# wespi-nano_4.net
KiCad netlist of a schematic drawn in EAGLE
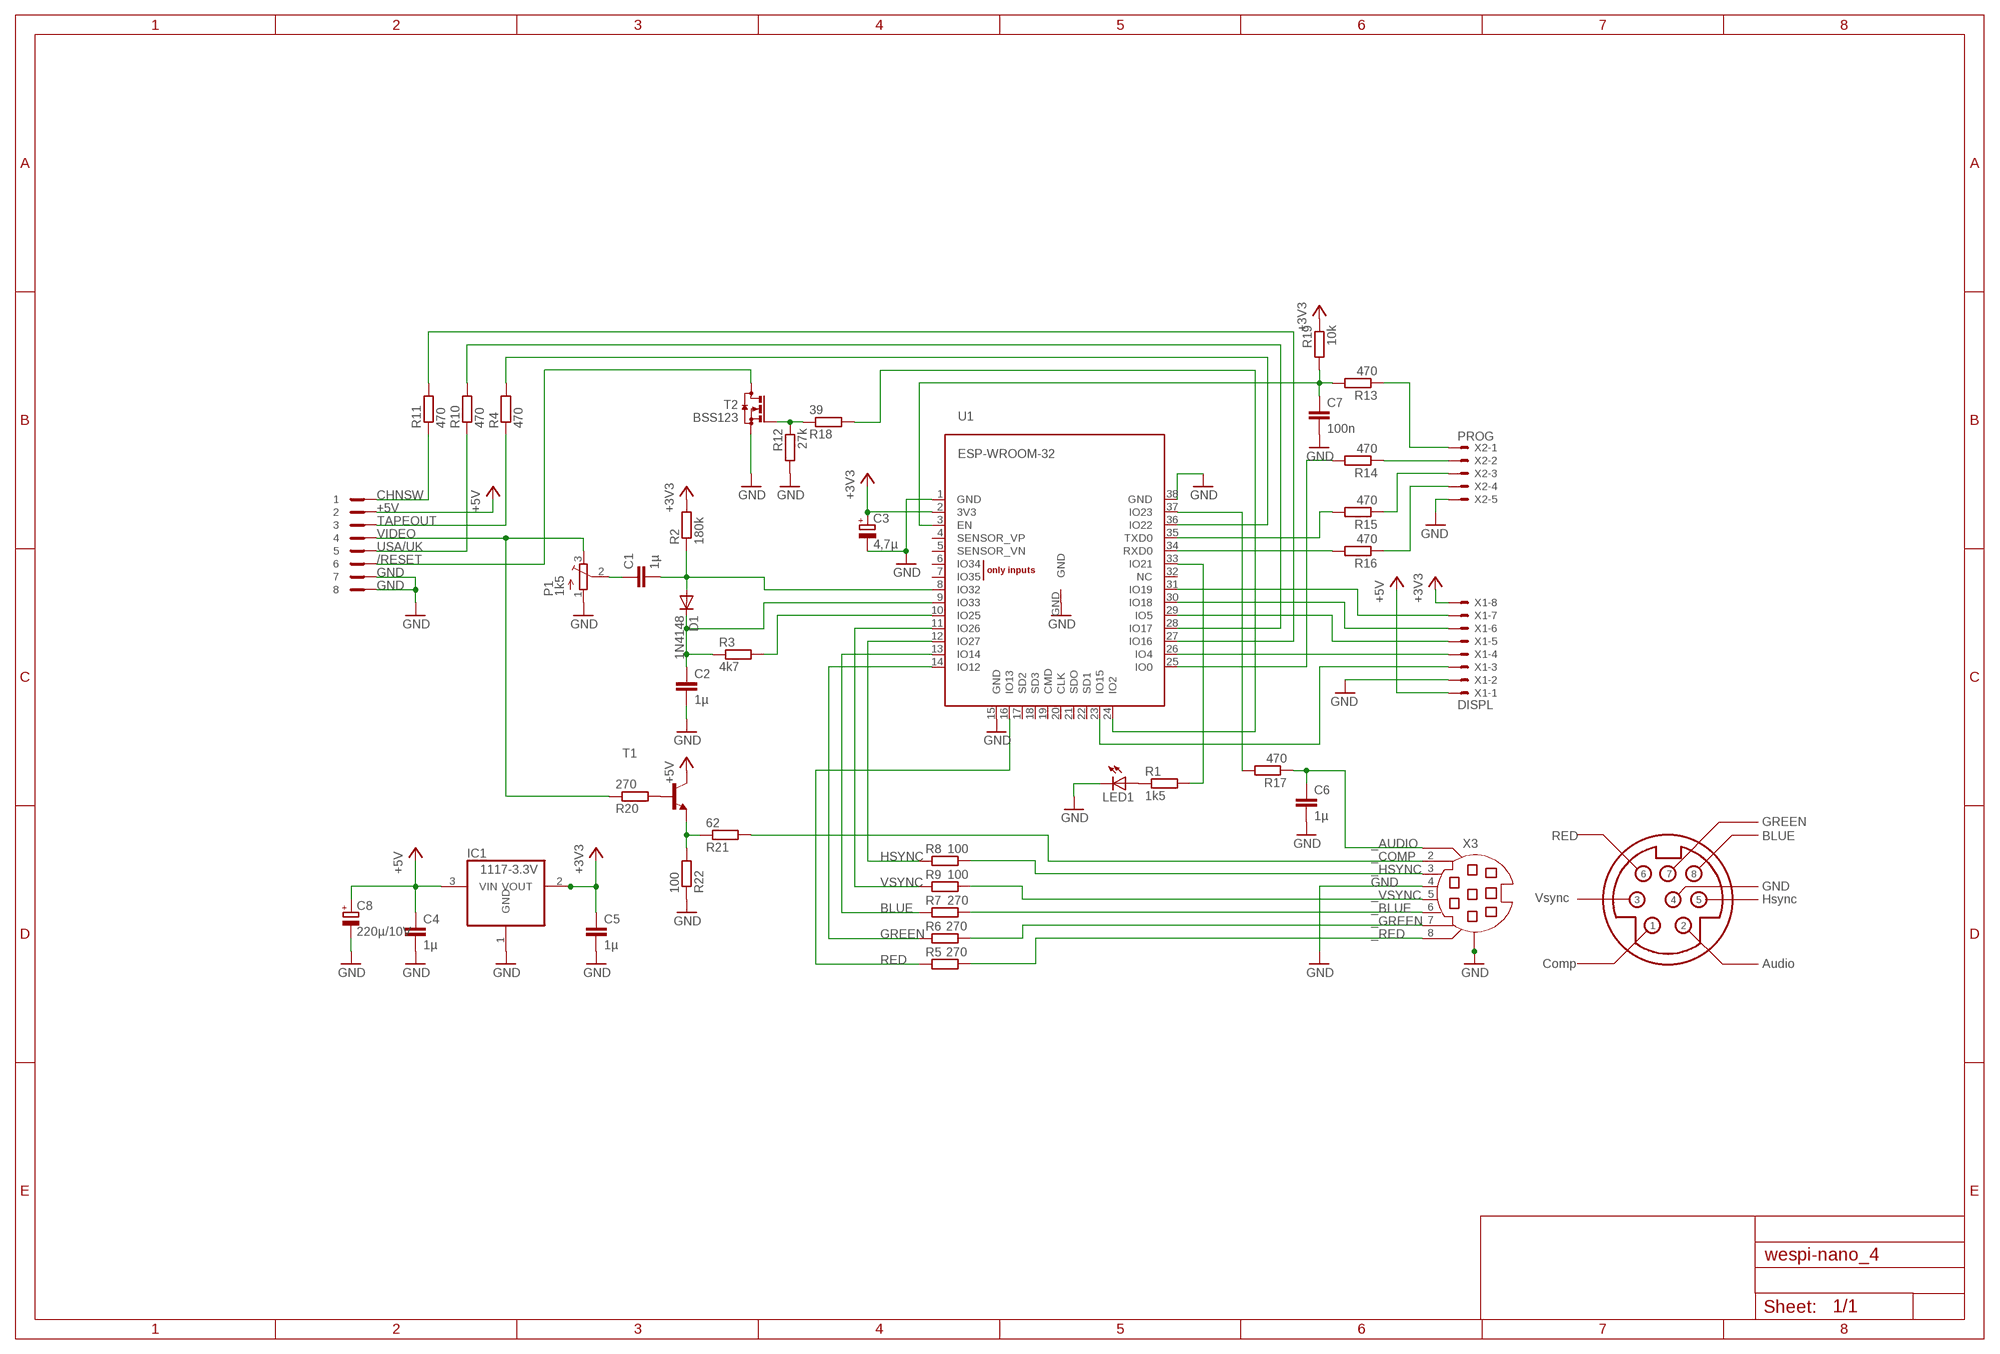
[diagram p0: schematic, sheet 1]

(export (version "E")
  (design (tool "Eeschema 10.0.6"))
  (components
    (comp (ref "C1")
      (value "1µ")
      (footprint "eagle-import:C0805")
      (libsource (lib "eagle-import") (part "C-EUC0805"))
    )
    (comp (ref "C2")
      (value "1µ")
      (footprint "eagle-import:C0805")
      (libsource (lib "eagle-import") (part "C-EUC0805"))
    )
    (comp (ref "C3")
      (value "4,7µ")
      (footprint "eagle-import:153CLV-0405")
      (libsource (lib "eagle-import") (part "CPOL-EU153CLV-0405"))
    )
    (comp (ref "C4")
      (value "1µ")
      (footprint "eagle-import:C0805")
      (libsource (lib "eagle-import") (part "C-EUC0805"))
    )
    (comp (ref "C5")
      (value "1µ")
      (footprint "eagle-import:C0805")
      (libsource (lib "eagle-import") (part "C-EUC0805"))
    )
    (comp (ref "C6")
      (value "1µ")
      (footprint "eagle-import:C0805")
      (libsource (lib "eagle-import") (part "C-EUC0805"))
    )
    (comp (ref "C7")
      (value "100n")
      (footprint "eagle-import:C0805")
      (libsource (lib "eagle-import") (part "C-EUC0805"))
    )
    (comp (ref "C8")
      (value "220µ/10V")
      (footprint "eagle-import:E2,5-6")
      (libsource (lib "eagle-import") (part "rcl_CPOL-EUE2.5-6"))
    )
    (comp (ref "D1")
      (value "1N4148")
      (footprint "eagle-import:SOD-123_MINI-SMA")
      (libsource (lib "eagle-import") (part "CGRM400-G1"))
    )
    (comp (ref "IC1")
      (value "1117-3.3V")
      (footprint "eagle-import:SOT223")
      (libsource (lib "eagle-import") (part "REG1117"))
    )
    (comp (ref "K6")
      (value "PINHEAD-2X4")
      (footprint "eagle-import:PINHEAD2X4")
      (libsource (lib "eagle-import") (part "PINHEAD-2X4"))
    )
    (comp (ref "LED1")
      (value "LEDSML0805")
      (footprint "eagle-import:SML0805")
      (libsource (lib "eagle-import") (part "LEDSML0805"))
    )
    (comp (ref "P1")
      (value "1k5")
      (footprint "eagle-import:3223G")
      (libsource (lib "eagle-import") (part "TRIM_EU-3223G"))
    )
    (comp (ref "R1")
      (value "1k5")
      (footprint "eagle-import:R0805")
      (libsource (lib "eagle-import") (part "R-EU_R0805"))
    )
    (comp (ref "R2")
      (value "180k")
      (footprint "eagle-import:R0805")
      (libsource (lib "eagle-import") (part "R-EU_R0805"))
    )
    (comp (ref "R3")
      (value "4k7")
      (footprint "eagle-import:R0805")
      (libsource (lib "eagle-import") (part "R-EU_R0805"))
    )
    (comp (ref "R4")
      (value "470")
      (footprint "eagle-import:R0805")
      (libsource (lib "eagle-import") (part "R-EU_R0805"))
    )
    (comp (ref "R5")
      (value "270")
      (footprint "eagle-import:R0805")
      (libsource (lib "eagle-import") (part "R-EU_R0805"))
    )
    (comp (ref "R6")
      (value "270")
      (footprint "eagle-import:R0805")
      (libsource (lib "eagle-import") (part "R-EU_R0805"))
    )
    (comp (ref "R7")
      (value "270")
      (footprint "eagle-import:R0805")
      (libsource (lib "eagle-import") (part "R-EU_R0805"))
    )
    (comp (ref "R8")
      (value "100")
      (footprint "eagle-import:R0805")
      (libsource (lib "eagle-import") (part "R-EU_R0805"))
    )
    (comp (ref "R9")
      (value "100")
      (footprint "eagle-import:R0805")
      (libsource (lib "eagle-import") (part "R-EU_R0805"))
    )
    (comp (ref "R10")
      (value "470")
      (footprint "eagle-import:R0805")
      (libsource (lib "eagle-import") (part "R-EU_R0805"))
    )
    (comp (ref "R11")
      (value "470")
      (footprint "eagle-import:R0805")
      (libsource (lib "eagle-import") (part "R-EU_R0805"))
    )
    (comp (ref "R12")
      (value "27k")
      (footprint "eagle-import:R0805")
      (libsource (lib "eagle-import") (part "R-EU_R0805"))
    )
    (comp (ref "R13")
      (value "470")
      (footprint "eagle-import:R0805")
      (libsource (lib "eagle-import") (part "R-EU_R0805"))
    )
    (comp (ref "R14")
      (value "470")
      (footprint "eagle-import:R0805")
      (libsource (lib "eagle-import") (part "R-EU_R0805"))
    )
    (comp (ref "R15")
      (value "470")
      (footprint "eagle-import:R0805")
      (libsource (lib "eagle-import") (part "R-EU_R0805"))
    )
    (comp (ref "R16")
      (value "470")
      (footprint "eagle-import:R0805")
      (libsource (lib "eagle-import") (part "R-EU_R0805"))
    )
    (comp (ref "R17")
      (value "470")
      (footprint "eagle-import:R0805")
      (libsource (lib "eagle-import") (part "R-EU_R0805"))
    )
    (comp (ref "R18")
      (value "39")
      (footprint "eagle-import:R0805")
      (libsource (lib "eagle-import") (part "R-EU_R0805"))
    )
    (comp (ref "R19")
      (value "10k")
      (footprint "eagle-import:R0805")
      (libsource (lib "eagle-import") (part "R-EU_R0805"))
    )
    (comp (ref "R20")
      (value "270")
      (footprint "eagle-import:R0805")
      (libsource (lib "eagle-import") (part "R-EU_R0805"))
    )
    (comp (ref "R21")
      (value "62")
      (footprint "eagle-import:R0805")
      (libsource (lib "eagle-import") (part "R-EU_R0805"))
    )
    (comp (ref "R22")
      (value "100")
      (footprint "eagle-import:R0805")
      (libsource (lib "eagle-import") (part "R-EU_R0805"))
    )
    (comp (ref "T1")
      (value "BC847-NPN-SOT23-BEC")
      (footprint "eagle-import:SOT23-BEC")
      (libsource (lib "eagle-import") (part "-NPN-SOT23-BECBC847"))
    )
    (comp (ref "T2")
      (value "BSS123")
      (footprint "eagle-import:SOT23")
      (libsource (lib "eagle-import") (part "BSS123"))
    )
    (comp (ref "U1")
      (value "ESP-WROOM-32")
      (footprint "eagle-import:ESP-WROOM-32")
      (libsource (lib "eagle-import") (part "ESP-WROOM-32"))
    )
    (comp (ref "X1")
      (value "DISPL")
      (footprint "eagle-import:53047-08")
      (fields (field (name "MPN") "53047-0810"))
      (libsource (lib "eagle-import") (part "53?-08047"))
    )
    (comp (ref "X2")
      (value "PROG")
      (footprint "eagle-import:53047-05")
      (fields (field (name "MF") "MOLEX") (field (name "MPN") "53047-0510"))
      (libsource (lib "eagle-import") (part "53?-05047"))
    )
    (comp (ref "X3")
      (value "MINI-DIN-8")
      (footprint "eagle-import:MINI-DIN-8")
      (libsource (lib "eagle-import") (part "MINI-DIN-8"))
    )
  )
  (nets
    (net (code "1") (name "+3V3") (class "Default")
      (node (ref "C3") (pin "+") (pinfunction "+_+") (pintype "passive"))
      (node (ref "C5") (pin "1") (pinfunction "1_1") (pintype "passive"))
      (node (ref "IC1") (pin "2") (pinfunction "VOUT_2") (pintype "output"))
      (node (ref "IC1") (pin "4") (pinfunction "VOUT1_4") (pintype "output"))
      (node (ref "R19") (pin "1") (pinfunction "1_1") (pintype "passive"))
      (node (ref "R2") (pin "2") (pinfunction "2_2") (pintype "passive"))
      (node (ref "U1") (pin "2") (pinfunction "3V3_2") (pintype "bidirectional"))
      (node (ref "X1") (pin "8") (pinfunction "S_8") (pintype "passive"))
    )
    (net (code "2") (name "+5V") (class "Default")
      (node (ref "C4") (pin "1") (pinfunction "1_1") (pintype "passive"))
      (node (ref "C8") (pin "+") (pinfunction "+_+") (pintype "passive"))
      (node (ref "IC1") (pin "3") (pinfunction "VIN_3") (pintype "input"))
      (node (ref "K6") (pin "2") (pinfunction "2_2") (pintype "bidirectional"))
      (node (ref "T1") (pin "C") (pinfunction "C_C") (pintype "passive"))
      (node (ref "X1") (pin "1") (pinfunction "S_1") (pintype "passive"))
    )
    (net (code "3") (name "/BLUE") (class "Default")
      (node (ref "R7") (pin "1") (pinfunction "1_1") (pintype "passive"))
      (node (ref "U1") (pin "13") (pinfunction "IO14_13") (pintype "bidirectional"))
    )
    (net (code "4") (name "/CHNSW") (class "Default")
      (node (ref "K6") (pin "1") (pinfunction "1_1") (pintype "bidirectional"))
      (node (ref "R11") (pin "1") (pinfunction "1_1") (pintype "passive"))
    )
    (net (code "5") (name "/GREEN") (class "Default")
      (node (ref "R6") (pin "1") (pinfunction "1_1") (pintype "passive"))
      (node (ref "U1") (pin "14") (pinfunction "IO12_14") (pintype "bidirectional"))
    )
    (net (code "6") (name "/HSYNC") (class "Default")
      (node (ref "R8") (pin "1") (pinfunction "1_1") (pintype "passive"))
      (node (ref "U1") (pin "12") (pinfunction "IO27_12") (pintype "bidirectional"))
    )
    (net (code "7") (name "/RED") (class "Default")
      (node (ref "R5") (pin "1") (pinfunction "1_1") (pintype "passive"))
      (node (ref "U1") (pin "16") (pinfunction "IO13_16") (pintype "bidirectional"))
    )
    (net (code "8") (name "/TAPEOUT") (class "Default")
      (node (ref "R4") (pin "2") (pinfunction "2_2") (pintype "passive"))
      (node (ref "U1") (pin "36") (pinfunction "IO22_36") (pintype "bidirectional"))
    )
    (net (code "9") (name "/USA{slash}UK") (class "Default")
      (node (ref "K6") (pin "5") (pinfunction "5_5") (pintype "bidirectional"))
      (node (ref "R10") (pin "1") (pinfunction "1_1") (pintype "passive"))
    )
    (net (code "10") (name "/VIDEO") (class "Default")
      (node (ref "K6") (pin "4") (pinfunction "4_4") (pintype "bidirectional"))
      (node (ref "P1") (pin "3") (pinfunction "E_3") (pintype "passive"))
      (node (ref "R20") (pin "1") (pinfunction "1_1") (pintype "passive"))
    )
    (net (code "11") (name "/VSYNC") (class "Default")
      (node (ref "R9") (pin "1") (pinfunction "1_1") (pintype "passive"))
      (node (ref "U1") (pin "11") (pinfunction "IO26_11") (pintype "bidirectional"))
    )
    (net (code "12") (name "/_AUDIO") (class "Default")
      (node (ref "C6") (pin "1") (pinfunction "1_1") (pintype "passive"))
      (node (ref "R17") (pin "1") (pinfunction "1_1") (pintype "passive"))
      (node (ref "X3") (pin "1") (pinfunction "1_1") (pintype "passive"))
    )
    (net (code "13") (name "/_BLUE") (class "Default")
      (node (ref "R7") (pin "2") (pinfunction "2_2") (pintype "passive"))
      (node (ref "X3") (pin "6") (pinfunction "6_6") (pintype "passive"))
    )
    (net (code "14") (name "/_COMP") (class "Default")
      (node (ref "R21") (pin "2") (pinfunction "2_2") (pintype "passive"))
      (node (ref "X3") (pin "2") (pinfunction "2_2") (pintype "passive"))
    )
    (net (code "15") (name "/_GREEN") (class "Default")
      (node (ref "R6") (pin "2") (pinfunction "2_2") (pintype "passive"))
      (node (ref "X3") (pin "7") (pinfunction "7_7") (pintype "passive"))
    )
    (net (code "16") (name "/_HSYNC") (class "Default")
      (node (ref "R8") (pin "2") (pinfunction "2_2") (pintype "passive"))
      (node (ref "X3") (pin "3") (pinfunction "3_3") (pintype "passive"))
    )
    (net (code "17") (name "/_RED") (class "Default")
      (node (ref "R5") (pin "2") (pinfunction "2_2") (pintype "passive"))
      (node (ref "X3") (pin "8") (pinfunction "8_8") (pintype "passive"))
    )
    (net (code "18") (name "/_VSYNC") (class "Default")
      (node (ref "R9") (pin "2") (pinfunction "2_2") (pintype "passive"))
      (node (ref "X3") (pin "5") (pinfunction "5_5") (pintype "passive"))
    )
    (net (code "19") (name "/{slash}RESET") (class "Default")
      (node (ref "K6") (pin "6") (pinfunction "6_6") (pintype "bidirectional"))
      (node (ref "T2") (pin "3") (pinfunction "D_3") (pintype "passive"))
    )
    (net (code "20") (name "GND") (class "Default")
      (node (ref "C2") (pin "2") (pinfunction "2_2") (pintype "passive"))
      (node (ref "C3") (pin "-") (pinfunction "-_-") (pintype "passive"))
      (node (ref "C4") (pin "2") (pinfunction "2_2") (pintype "passive"))
      (node (ref "C5") (pin "2") (pinfunction "2_2") (pintype "passive"))
      (node (ref "C6") (pin "2") (pinfunction "2_2") (pintype "passive"))
      (node (ref "C7") (pin "2") (pinfunction "2_2") (pintype "passive"))
      (node (ref "C8") (pin "-") (pinfunction "-_-") (pintype "passive"))
      (node (ref "IC1") (pin "1") (pinfunction "GND_1") (pintype "power_in"))
      (node (ref "K6") (pin "7") (pinfunction "7_7") (pintype "bidirectional"))
      (node (ref "K6") (pin "8") (pinfunction "8_8") (pintype "bidirectional"))
      (node (ref "LED1") (pin "C") (pinfunction "C_C") (pintype "passive"))
      (node (ref "P1") (pin "1") (pinfunction "A_1") (pintype "passive"))
      (node (ref "R12") (pin "2") (pinfunction "2_2") (pintype "passive"))
      (node (ref "R22") (pin "1") (pinfunction "1_1") (pintype "passive"))
      (node (ref "T2") (pin "2") (pinfunction "S_2") (pintype "passive"))
      (node (ref "U1") (pin "1") (pinfunction "GND_1") (pintype "bidirectional"))
      (node (ref "U1") (pin "15") (pinfunction "GND_15") (pintype "bidirectional"))
      (node (ref "U1") (pin "38") (pinfunction "GND_38") (pintype "bidirectional"))
      (node (ref "U1") (pin "GND") (pinfunction "GND_GND") (pintype "bidirectional"))
      (node (ref "X1") (pin "2") (pinfunction "S_2") (pintype "passive"))
      (node (ref "X2") (pin "5") (pinfunction "S_5") (pintype "passive"))
      (node (ref "X3") (pin "4") (pinfunction "4_4") (pintype "passive"))
      (node (ref "X3") (pin "G") (pinfunction "G1_G") (pintype "passive"))
      (node (ref "X3") (pin "G1") (pinfunction "G2_G1") (pintype "passive"))
      (node (ref "X3") (pin "G2") (pinfunction "G3_G2") (pintype "passive"))
    )
    (net (code "21") (name "Net-(K6-Pad3)") (class "Default")
      (node (ref "K6") (pin "3") (pinfunction "3_3") (pintype "bidirectional"))
      (node (ref "R4") (pin "1") (pinfunction "1_1") (pintype "passive"))
    )
    (net (code "22") (name "Net-(LED1-PadA)") (class "Default")
      (node (ref "LED1") (pin "A") (pinfunction "A_A") (pintype "passive"))
      (node (ref "R1") (pin "1") (pinfunction "1_1") (pintype "passive"))
    )
    (net (code "23") (name "Net-(P1-S)") (class "Default")
      (node (ref "C1") (pin "1") (pinfunction "1_1") (pintype "passive"))
      (node (ref "P1") (pin "2") (pinfunction "S_2") (pintype "passive"))
    )
    (net (code "24") (name "Net-(R20-Pad2)") (class "Default")
      (node (ref "R20") (pin "2") (pinfunction "2_2") (pintype "passive"))
      (node (ref "T1") (pin "B") (pinfunction "B_B") (pintype "passive"))
    )
    (net (code "25") (name "Net-(R21-Pad1)") (class "Default")
      (node (ref "R21") (pin "1") (pinfunction "1_1") (pintype "passive"))
      (node (ref "R22") (pin "2") (pinfunction "2_2") (pintype "passive"))
      (node (ref "T1") (pin "E") (pinfunction "E_E") (pintype "passive"))
    )
    (net (code "26") (name "Net-(T2-G)") (class "Default")
      (node (ref "R12") (pin "1") (pinfunction "1_1") (pintype "passive"))
      (node (ref "R18") (pin "1") (pinfunction "1_1") (pintype "passive"))
      (node (ref "T2") (pin "1") (pinfunction "G_1") (pintype "passive"))
    )
    (net (code "27") (name "Net-(U1-EN)") (class "Default")
      (node (ref "C7") (pin "1") (pinfunction "1_1") (pintype "passive"))
      (node (ref "R13") (pin "2") (pinfunction "2_2") (pintype "passive"))
      (node (ref "R19") (pin "2") (pinfunction "2_2") (pintype "passive"))
      (node (ref "U1") (pin "3") (pinfunction "EN_3") (pintype "bidirectional"))
    )
    (net (code "28") (name "Net-(U1-IO0)") (class "Default")
      (node (ref "R14") (pin "2") (pinfunction "2_2") (pintype "passive"))
      (node (ref "U1") (pin "25") (pinfunction "IO0_25") (pintype "bidirectional"))
    )
    (net (code "29") (name "Net-(U1-IO2)") (class "Default")
      (node (ref "R18") (pin "2") (pinfunction "2_2") (pintype "passive"))
      (node (ref "U1") (pin "24") (pinfunction "IO2_24") (pintype "bidirectional"))
    )
    (net (code "30") (name "Net-(U1-IO4)") (class "Default")
      (node (ref "U1") (pin "26") (pinfunction "IO4_26") (pintype "bidirectional"))
      (node (ref "X1") (pin "4") (pinfunction "S_4") (pintype "passive"))
    )
    (net (code "31") (name "Net-(U1-IO5)") (class "Default")
      (node (ref "U1") (pin "29") (pinfunction "IO5_29") (pintype "bidirectional"))
      (node (ref "X1") (pin "5") (pinfunction "S_5") (pintype "passive"))
    )
    (net (code "32") (name "Net-(U1-IO15)") (class "Default")
      (node (ref "U1") (pin "23") (pinfunction "IO15_23") (pintype "bidirectional"))
      (node (ref "X1") (pin "3") (pinfunction "S_3") (pintype "passive"))
    )
    (net (code "33") (name "Net-(U1-IO16)") (class "Default")
      (node (ref "R11") (pin "2") (pinfunction "2_2") (pintype "passive"))
      (node (ref "U1") (pin "27") (pinfunction "IO16_27") (pintype "bidirectional"))
    )
    (net (code "34") (name "Net-(U1-IO17)") (class "Default")
      (node (ref "R10") (pin "2") (pinfunction "2_2") (pintype "passive"))
      (node (ref "U1") (pin "28") (pinfunction "IO17_28") (pintype "bidirectional"))
    )
    (net (code "35") (name "Net-(U1-IO18)") (class "Default")
      (node (ref "U1") (pin "30") (pinfunction "IO18_30") (pintype "bidirectional"))
      (node (ref "X1") (pin "6") (pinfunction "S_6") (pintype "passive"))
    )
    (net (code "36") (name "Net-(U1-IO19)") (class "Default")
      (node (ref "U1") (pin "31") (pinfunction "IO19_31") (pintype "bidirectional"))
      (node (ref "X1") (pin "7") (pinfunction "S_7") (pintype "passive"))
    )
    (net (code "37") (name "Net-(U1-IO21)") (class "Default")
      (node (ref "R1") (pin "2") (pinfunction "2_2") (pintype "passive"))
      (node (ref "U1") (pin "33") (pinfunction "IO21_33") (pintype "bidirectional"))
    )
    (net (code "38") (name "Net-(U1-IO23)") (class "Default")
      (node (ref "R17") (pin "2") (pinfunction "2_2") (pintype "passive"))
      (node (ref "U1") (pin "37") (pinfunction "IO23_37") (pintype "bidirectional"))
    )
    (net (code "39") (name "Net-(U1-IO25)") (class "Default")
      (node (ref "R3") (pin "2") (pinfunction "2_2") (pintype "passive"))
      (node (ref "U1") (pin "10") (pinfunction "IO25_10") (pintype "bidirectional"))
    )
    (net (code "40") (name "Net-(U1-IO32)") (class "Default")
      (node (ref "C1") (pin "2") (pinfunction "2_2") (pintype "passive"))
      (node (ref "D1") (pin "A") (pinfunction "A_A") (pintype "passive"))
      (node (ref "R2") (pin "1") (pinfunction "1_1") (pintype "passive"))
      (node (ref "U1") (pin "8") (pinfunction "IO32_8") (pintype "bidirectional"))
    )
    (net (code "41") (name "Net-(U1-IO33)") (class "Default")
      (node (ref "C2") (pin "1") (pinfunction "1_1") (pintype "passive"))
      (node (ref "D1") (pin "C") (pinfunction "C_C") (pintype "passive"))
      (node (ref "R3") (pin "1") (pinfunction "1_1") (pintype "passive"))
      (node (ref "U1") (pin "9") (pinfunction "IO33_9") (pintype "bidirectional"))
    )
    (net (code "42") (name "Net-(U1-RXD0)") (class "Default")
      (node (ref "R16") (pin "2") (pinfunction "2_2") (pintype "passive"))
      (node (ref "U1") (pin "34") (pinfunction "RXD0_34") (pintype "bidirectional"))
    )
    (net (code "43") (name "Net-(U1-TXD0)") (class "Default")
      (node (ref "R15") (pin "2") (pinfunction "2_2") (pintype "passive"))
      (node (ref "U1") (pin "35") (pinfunction "TXD0_35") (pintype "bidirectional"))
    )
    (net (code "44") (name "Net-(X2A-S)") (class "Default")
      (node (ref "R13") (pin "1") (pinfunction "1_1") (pintype "passive"))
      (node (ref "X2") (pin "1") (pinfunction "S_1") (pintype "passive"))
    )
    (net (code "45") (name "Net-(X2B-S)") (class "Default")
      (node (ref "R14") (pin "1") (pinfunction "1_1") (pintype "passive"))
      (node (ref "X2") (pin "2") (pinfunction "S_2") (pintype "passive"))
    )
    (net (code "46") (name "Net-(X2C-S)") (class "Default")
      (node (ref "R15") (pin "1") (pinfunction "1_1") (pintype "passive"))
      (node (ref "X2") (pin "3") (pinfunction "S_3") (pintype "passive"))
    )
    (net (code "47") (name "Net-(X2D-S)") (class "Default")
      (node (ref "R16") (pin "1") (pinfunction "1_1") (pintype "passive"))
      (node (ref "X2") (pin "4") (pinfunction "S_4") (pintype "passive"))
    )
    (net (code "48") (name "unconnected-(U1-CLK-Pad20)") (class "Default")
      (node (ref "U1") (pin "20") (pinfunction "CLK_20") (pintype "bidirectional"))
    )
    (net (code "49") (name "unconnected-(U1-CMD-Pad19)") (class "Default")
      (node (ref "U1") (pin "19") (pinfunction "CMD_19") (pintype "bidirectional"))
    )
    (net (code "50") (name "unconnected-(U1-IO34-Pad6)") (class "Default")
      (node (ref "U1") (pin "6") (pinfunction "IO34_6") (pintype "input"))
    )
    (net (code "51") (name "unconnected-(U1-IO35-Pad7)") (class "Default")
      (node (ref "U1") (pin "7") (pinfunction "IO35_7") (pintype "input"))
    )
    (net (code "52") (name "unconnected-(U1-NC-Pad32)") (class "Default")
      (node (ref "U1") (pin "32") (pinfunction "NC_32") (pintype "bidirectional"))
    )
    (net (code "53") (name "unconnected-(U1-SD1-Pad22)") (class "Default")
      (node (ref "U1") (pin "22") (pinfunction "SD1_22") (pintype "bidirectional"))
    )
    (net (code "54") (name "unconnected-(U1-SD2-Pad17)") (class "Default")
      (node (ref "U1") (pin "17") (pinfunction "SD2_17") (pintype "bidirectional"))
    )
    (net (code "55") (name "unconnected-(U1-SD3-Pad18)") (class "Default")
      (node (ref "U1") (pin "18") (pinfunction "SD3_18") (pintype "bidirectional"))
    )
    (net (code "56") (name "unconnected-(U1-SDO-Pad21)") (class "Default")
      (node (ref "U1") (pin "21") (pinfunction "SDO_21") (pintype "bidirectional"))
    )
    (net (code "57") (name "unconnected-(U1-SENSOR_VN-Pad5)") (class "Default")
      (node (ref "U1") (pin "5") (pinfunction "SENSOR_VN_5") (pintype "input"))
    )
    (net (code "58") (name "unconnected-(U1-SENSOR_VP-Pad4)") (class "Default")
      (node (ref "U1") (pin "4") (pinfunction "SENSOR_VP_4") (pintype "input"))
    )
  )
)
